# LED.net
KiCad netlist of a schematic drawn in EAGLE
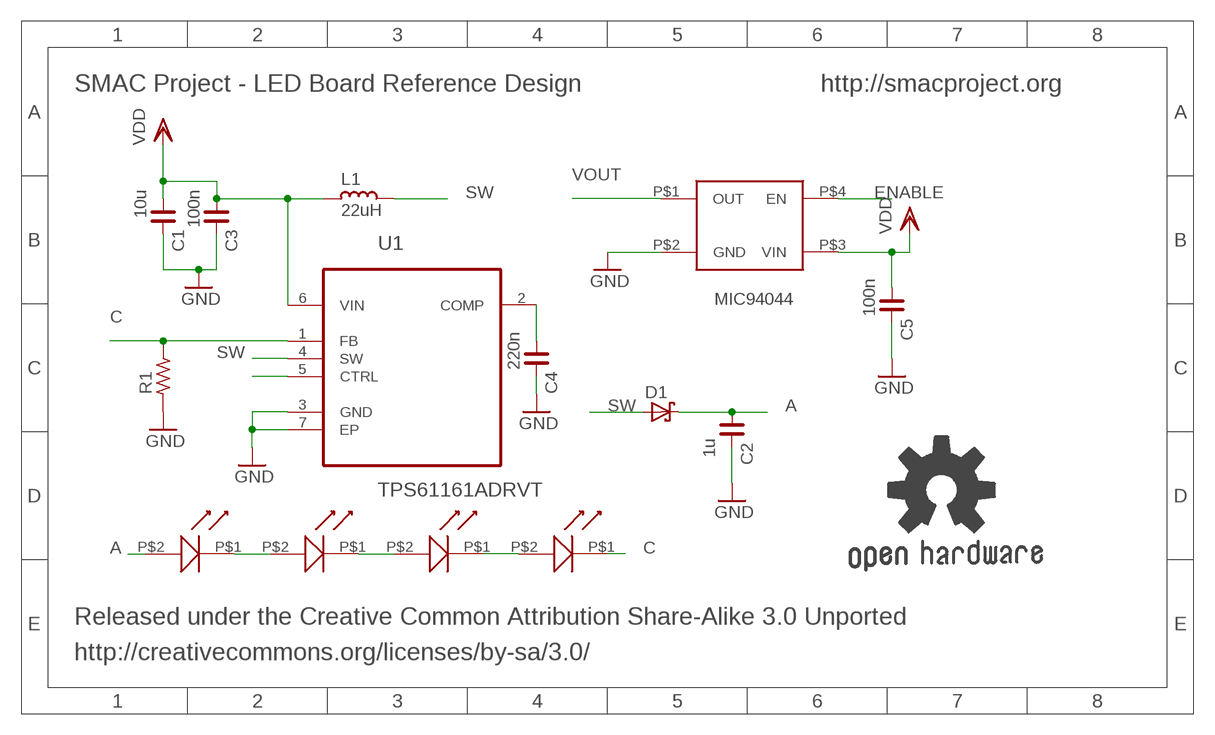
[diagram p0: schematic, sheet 1]

(export (version "E")
  (design (tool "Eeschema 10.0.6"))
  (components
    (comp (ref "C1")
      (value "10u")
      (footprint "eagle-import:C0402")
      (libsource (lib "eagle-import") (part "C_0402"))
    )
    (comp (ref "C2")
      (value "1u")
      (footprint "eagle-import:C0402")
      (libsource (lib "eagle-import") (part "C_0402"))
    )
    (comp (ref "C3")
      (value "100n")
      (footprint "eagle-import:C0402")
      (libsource (lib "eagle-import") (part "C_0402"))
    )
    (comp (ref "C4")
      (value "220n")
      (footprint "eagle-import:C0402")
      (libsource (lib "eagle-import") (part "C_0402"))
    )
    (comp (ref "C5")
      (value "100n")
      (footprint "eagle-import:C0402")
      (libsource (lib "eagle-import") (part "C_0402"))
    )
    (comp (ref "D1")
      (value "SCHOTTKY-DIODE")
      (footprint "eagle-import:SOD123FL")
      (libsource (lib "eagle-import") (part "SCHOTTKY-DIODE"))
    )
    (comp (ref "GOLD_ORB_SM2")
      (value "OSHWLOGO_REF_SM")
      (footprint "eagle-import:OSHW2REF")
      (libsource (lib "eagle-import") (part "OSHWLOGO_REF_SM"))
    )
    (comp (ref "L1")
      (value "22uH")
      (footprint "eagle-import:L0805")
      (libsource (lib "eagle-import") (part "L_0805"))
    )
    (comp (ref "R1")
      (value "R_0402")
      (footprint "eagle-import:R0402")
      (libsource (lib "eagle-import") (part "R_0402"))
    )
    (comp (ref "U$1")
      (value "LED_NICHIA")
      (footprint "eagle-import:LED_SMT_NICHIA")
      (libsource (lib "eagle-import") (part "LED_NICHIA"))
    )
    (comp (ref "U$2")
      (value "LED_NICHIA")
      (footprint "eagle-import:LED_SMT_NICHIA")
      (libsource (lib "eagle-import") (part "LED_NICHIA"))
    )
    (comp (ref "U$3")
      (value "LED_NICHIA")
      (footprint "eagle-import:LED_SMT_NICHIA")
      (libsource (lib "eagle-import") (part "LED_NICHIA"))
    )
    (comp (ref "U$4")
      (value "LED_NICHIA")
      (footprint "eagle-import:LED_SMT_NICHIA")
      (libsource (lib "eagle-import") (part "LED_NICHIA"))
    )
    (comp (ref "U$5")
      (value "MIC94044")
      (footprint "eagle-import:MIC94045YFL_FOOTPRINT")
      (libsource (lib "eagle-import") (part "MIC94044"))
    )
    (comp (ref "U1")
      (value "TPS61161ADRVT")
      (footprint "eagle-import:SON65P200X200X80-7N")
      (libsource (lib "eagle-import") (part "TPS61161ADRVT"))
    )
  )
  (nets
    (net (code "1") (name "/A") (class "Default")
      (node (ref "C2") (pin "1") (pinfunction "1_1") (pintype "passive"))
      (node (ref "D1") (pin "C") (pinfunction "C_C") (pintype "passive"))
      (node (ref "U$4") (pin "P$2") (pinfunction "A_P$2") (pintype "bidirectional"))
    )
    (net (code "2") (name "/C") (class "Default")
      (node (ref "R1") (pin "2") (pinfunction "2_2") (pintype "passive"))
      (node (ref "U$2") (pin "P$1") (pinfunction "K_P$1") (pintype "bidirectional"))
      (node (ref "U1") (pin "1") (pinfunction "FB_1") (pintype "input"))
    )
    (net (code "3") (name "/ENABLE") (class "Default")
      (node (ref "U$5") (pin "P$4") (pinfunction "EN_P$4") (pintype "bidirectional"))
    )
    (net (code "4") (name "/SW") (class "Default")
      (node (ref "D1") (pin "A") (pinfunction "A_A") (pintype "passive"))
      (node (ref "L1") (pin "1") (pinfunction "1_1") (pintype "passive"))
      (node (ref "U1") (pin "4") (pinfunction "SW_4") (pintype "input"))
    )
    (net (code "5") (name "/VOUT") (class "Default")
      (node (ref "U$5") (pin "P$1") (pinfunction "OUT_P$1") (pintype "bidirectional"))
    )
    (net (code "6") (name "GND") (class "Default")
      (node (ref "C1") (pin "2") (pinfunction "2_2") (pintype "passive"))
      (node (ref "C2") (pin "2") (pinfunction "2_2") (pintype "passive"))
      (node (ref "C3") (pin "2") (pinfunction "2_2") (pintype "passive"))
      (node (ref "C4") (pin "2") (pinfunction "2_2") (pintype "passive"))
      (node (ref "C5") (pin "2") (pinfunction "2_2") (pintype "passive"))
      (node (ref "R1") (pin "1") (pinfunction "1_1") (pintype "passive"))
      (node (ref "U$5") (pin "P$2") (pinfunction "GND_P$2") (pintype "bidirectional"))
      (node (ref "U1") (pin "3") (pinfunction "GND_3") (pintype "passive"))
      (node (ref "U1") (pin "7") (pinfunction "EP_7") (pintype "passive"))
    )
    (net (code "7") (name "Net-(U$1-A)") (class "Default")
      (node (ref "U$1") (pin "P$2") (pinfunction "A_P$2") (pintype "bidirectional"))
      (node (ref "U$4") (pin "P$1") (pinfunction "K_P$1") (pintype "bidirectional"))
    )
    (net (code "8") (name "Net-(U$1-K)") (class "Default")
      (node (ref "U$1") (pin "P$1") (pinfunction "K_P$1") (pintype "bidirectional"))
      (node (ref "U$3") (pin "P$2") (pinfunction "A_P$2") (pintype "bidirectional"))
    )
    (net (code "9") (name "Net-(U$2-A)") (class "Default")
      (node (ref "U$2") (pin "P$2") (pinfunction "A_P$2") (pintype "bidirectional"))
      (node (ref "U$3") (pin "P$1") (pinfunction "K_P$1") (pintype "bidirectional"))
    )
    (net (code "10") (name "Net-(U1-COMP)") (class "Default")
      (node (ref "C4") (pin "1") (pinfunction "1_1") (pintype "passive"))
      (node (ref "U1") (pin "2") (pinfunction "COMP_2") (pintype "output"))
    )
    (net (code "11") (name "VDD") (class "Default")
      (node (ref "C1") (pin "1") (pinfunction "1_1") (pintype "passive"))
      (node (ref "C3") (pin "1") (pinfunction "1_1") (pintype "passive"))
      (node (ref "C5") (pin "1") (pinfunction "1_1") (pintype "passive"))
      (node (ref "L1") (pin "2") (pinfunction "2_2") (pintype "passive"))
      (node (ref "U$5") (pin "P$3") (pinfunction "VIN_P$3") (pintype "bidirectional"))
      (node (ref "U1") (pin "6") (pinfunction "VIN_6") (pintype "power_in"))
    )
    (net (code "12") (name "unconnected-(U1-CTRL-Pad5)") (class "Default")
      (node (ref "U1") (pin "5") (pinfunction "CTRL_5") (pintype "input"))
    )
  )
)
